# SCH_JTAG_14P_10P_2022-09-26.net
KiCad netlist of a schematic drawn in EasyEDA
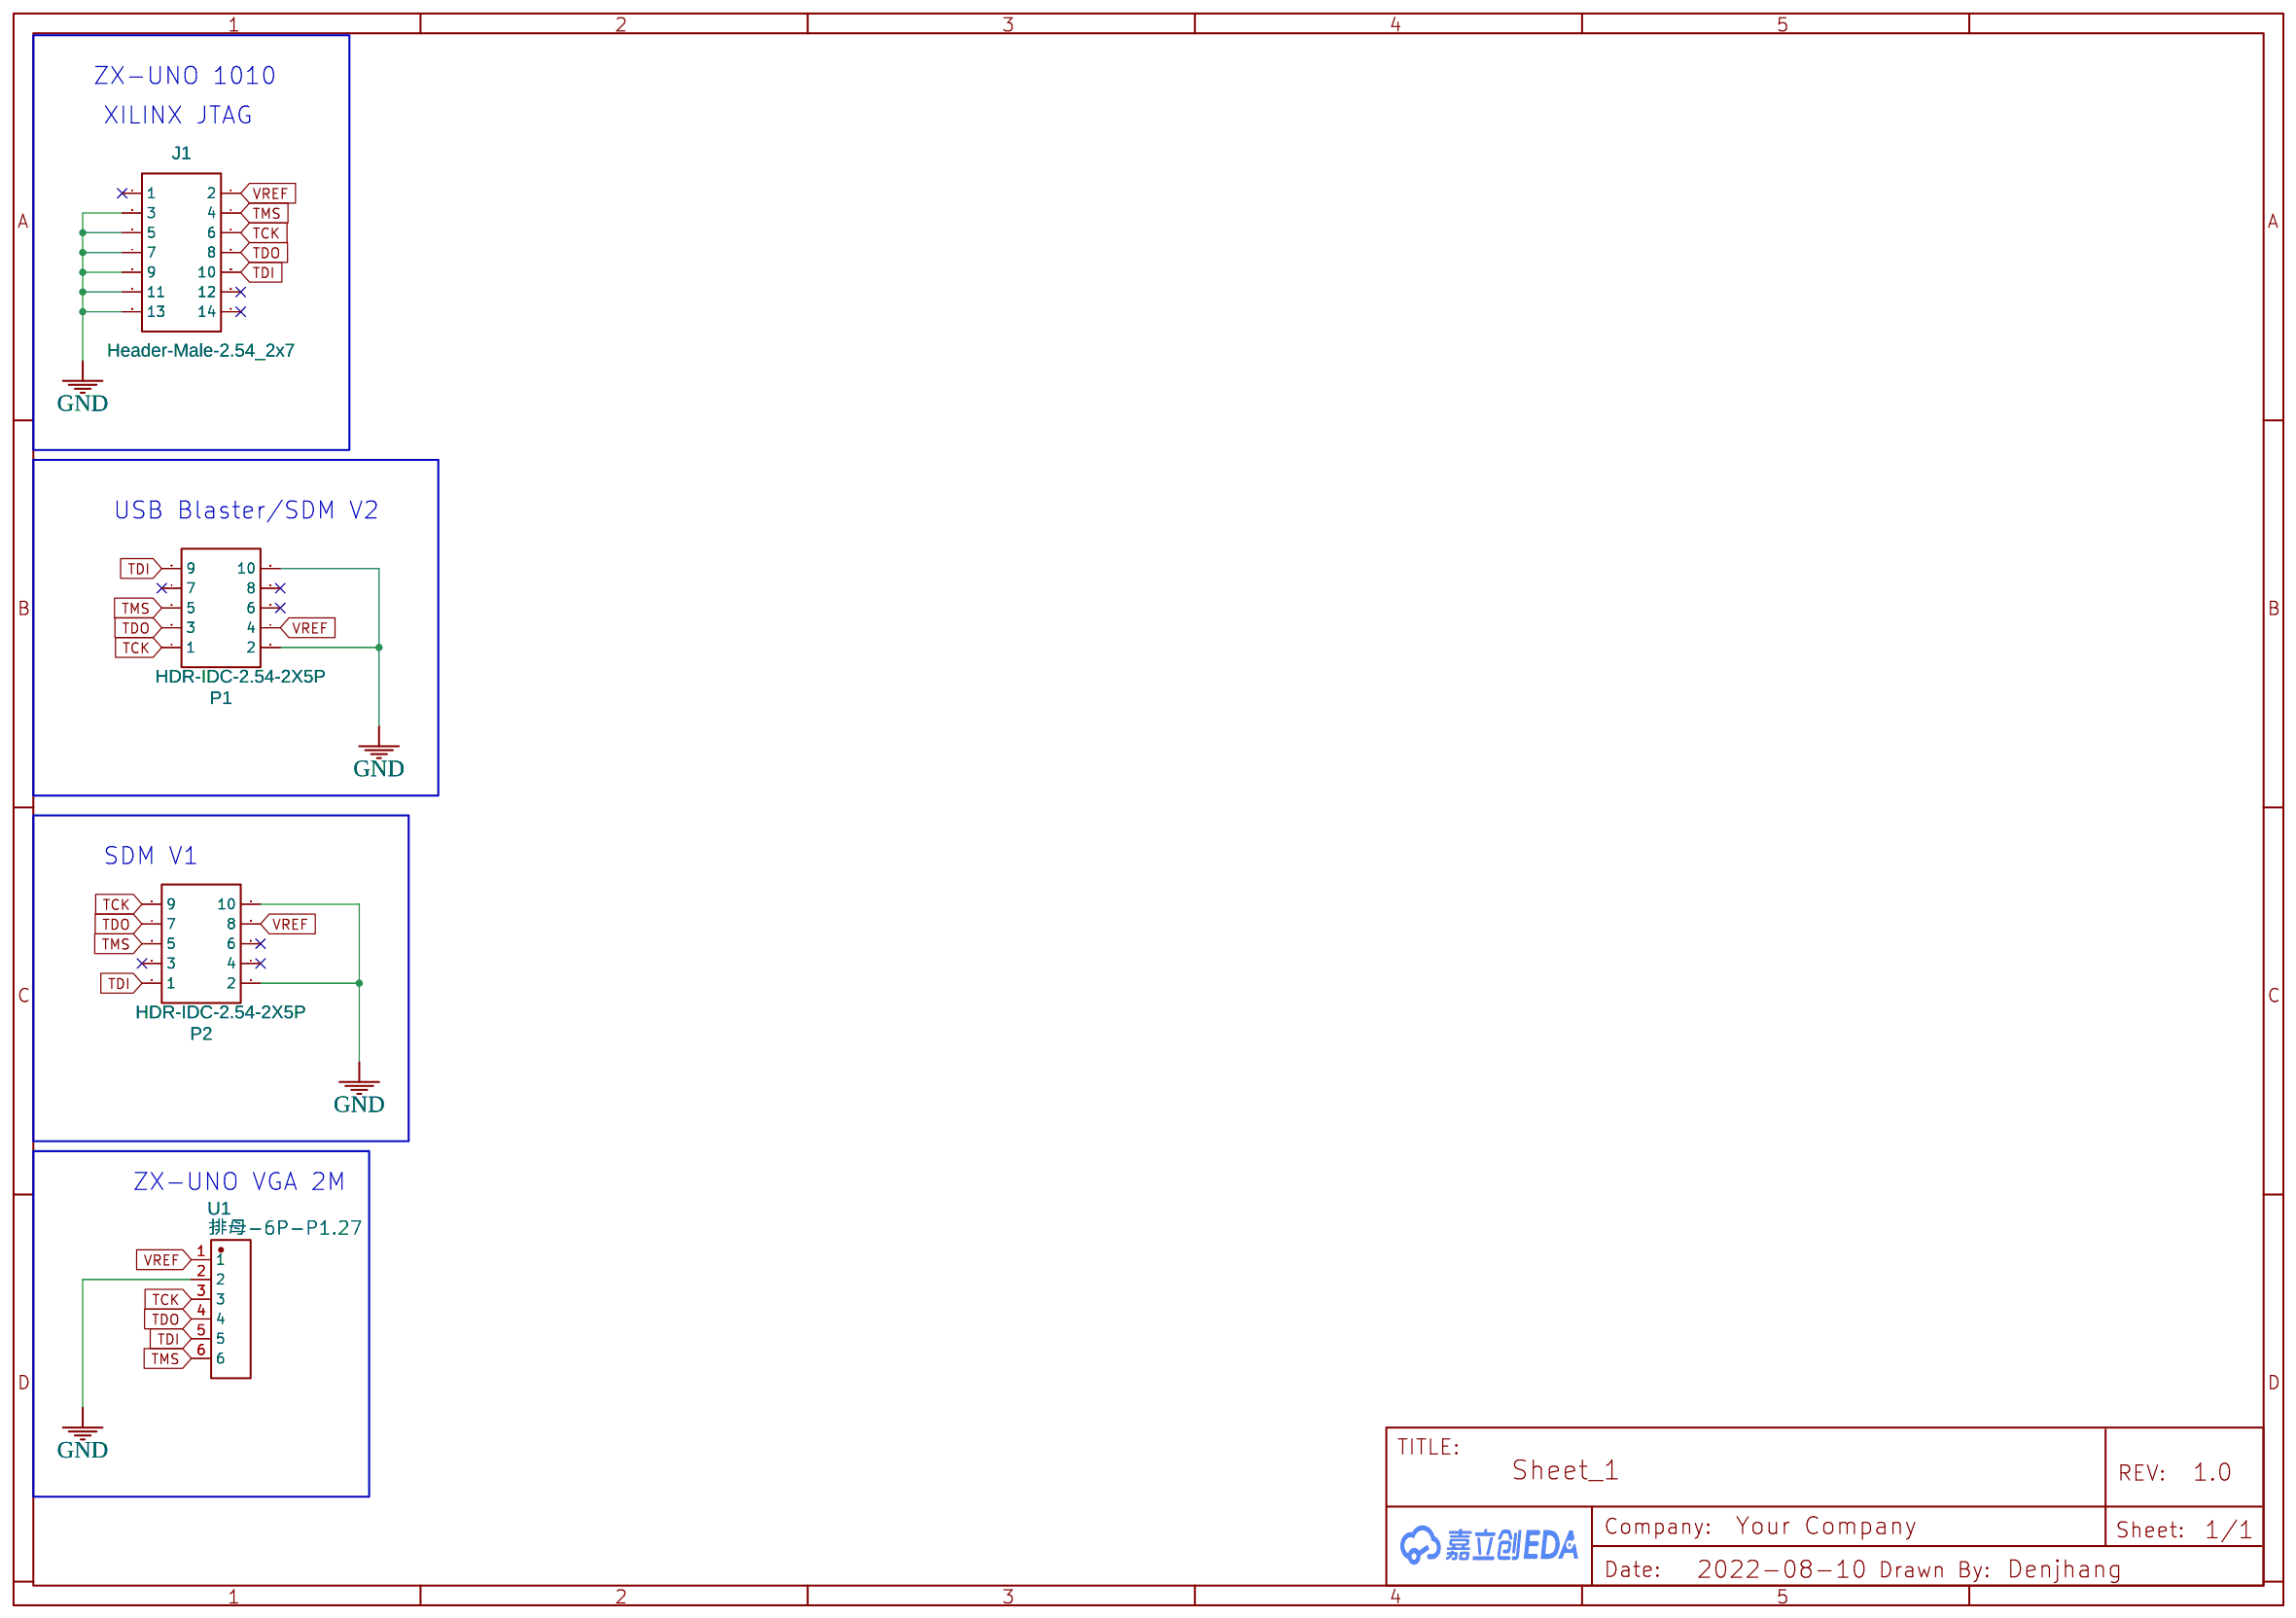
[diagram p0: schematic sheet]

(export (version "E")
  (design (tool "Eeschema 10.0.6"))
  (components
    (comp (ref "J1")
      (value "Header-Male-2.54_2x7")
      (fields
        (field (name "BOM_Manufacturer Part") "Double row of needle2X7P 2.54mm")
        (field (name "BOM_Supplier Part") "C71397")
      )
      (libsource (lib "") (part "Header-Male-2.54_2x7"))
    )
    (comp (ref "P1")
      (value "HDR-IDC-2.54-2X5P")
      (fields
        (field (name "BOM_Manufacturer Part") "IDC Box 2.54mm 2X5P")
        (field (name "BOM_Supplier Part") "C5665")
      )
      (libsource (lib "") (part "HDR-IDC-2.54-2X5P"))
    )
    (comp (ref "P2")
      (value "HDR-IDC-2.54-2X5P")
      (fields
        (field (name "BOM_Manufacturer Part") "IDC Box 2.54mm 2X5P")
        (field (name "BOM_Supplier Part") "C5665")
      )
      (libsource (lib "") (part "HDR-IDC-2.54-2X5P"))
    )
    (comp (ref "U1")
      (value "排母-6P-P1.27")
      (fields
        (field (name "BOM_Manufacturer Part") "KH-1.27FH-1X6P-H4.3")
        (field (name "BOM_Supplier Part") "C2938382")
      )
      (libsource (lib "") (part "排母-6P-P1.27"))
    )
  )
  (nets
    (net (code "1") (name "GND") (class "Default")
      (node (ref "J1") (pin "11") (pinfunction "11_11") (pintype "input"))
      (node (ref "J1") (pin "13") (pinfunction "13_13") (pintype "input"))
      (node (ref "J1") (pin "3") (pinfunction "3_3") (pintype "input"))
      (node (ref "J1") (pin "5") (pinfunction "5_5") (pintype "input"))
      (node (ref "J1") (pin "7") (pinfunction "7_7") (pintype "input"))
      (node (ref "J1") (pin "9") (pinfunction "9_9") (pintype "input"))
      (node (ref "P1") (pin "10") (pinfunction "10_10") (pintype "unspecified"))
      (node (ref "P1") (pin "2") (pinfunction "2_2") (pintype "unspecified"))
      (node (ref "P2") (pin "10") (pinfunction "10_10") (pintype "unspecified"))
      (node (ref "P2") (pin "2") (pinfunction "2_2") (pintype "unspecified"))
      (node (ref "U1") (pin "2") (pinfunction "2_2") (pintype "unspecified"))
    )
    (net (code "2") (name "TCK") (class "Default")
      (node (ref "J1") (pin "6") (pinfunction "6_6") (pintype "input"))
      (node (ref "P1") (pin "1") (pinfunction "1_1") (pintype "unspecified"))
      (node (ref "P2") (pin "9") (pinfunction "9_9") (pintype "unspecified"))
      (node (ref "U1") (pin "3") (pinfunction "3_3") (pintype "unspecified"))
    )
    (net (code "3") (name "TDI") (class "Default")
      (node (ref "J1") (pin "10") (pinfunction "10_10") (pintype "input"))
      (node (ref "P1") (pin "9") (pinfunction "9_9") (pintype "unspecified"))
      (node (ref "P2") (pin "1") (pinfunction "1_1") (pintype "unspecified"))
      (node (ref "U1") (pin "5") (pinfunction "5_5") (pintype "unspecified"))
    )
    (net (code "4") (name "TDO") (class "Default")
      (node (ref "J1") (pin "8") (pinfunction "8_8") (pintype "input"))
      (node (ref "P1") (pin "3") (pinfunction "3_3") (pintype "unspecified"))
      (node (ref "P2") (pin "7") (pinfunction "7_7") (pintype "unspecified"))
      (node (ref "U1") (pin "4") (pinfunction "4_4") (pintype "unspecified"))
    )
    (net (code "5") (name "TMS") (class "Default")
      (node (ref "J1") (pin "4") (pinfunction "4_4") (pintype "input"))
      (node (ref "P1") (pin "5") (pinfunction "5_5") (pintype "unspecified"))
      (node (ref "P2") (pin "5") (pinfunction "5_5") (pintype "unspecified"))
      (node (ref "U1") (pin "6") (pinfunction "6_6") (pintype "unspecified"))
    )
    (net (code "6") (name "VREF") (class "Default")
      (node (ref "J1") (pin "2") (pinfunction "2_2") (pintype "input"))
      (node (ref "P1") (pin "4") (pinfunction "4_4") (pintype "unspecified"))
      (node (ref "P2") (pin "8") (pinfunction "8_8") (pintype "unspecified"))
      (node (ref "U1") (pin "1") (pinfunction "1_1") (pintype "unspecified"))
    )
    (net (code "7") (name "unconnected-(J1-Pad1)") (class "Default")
      (node (ref "J1") (pin "1") (pinfunction "1_1") (pintype "input+no_connect"))
    )
    (net (code "8") (name "unconnected-(J1-Pad12)") (class "Default")
      (node (ref "J1") (pin "12") (pinfunction "12_12") (pintype "input+no_connect"))
    )
    (net (code "9") (name "unconnected-(J1-Pad14)") (class "Default")
      (node (ref "J1") (pin "14") (pinfunction "14_14") (pintype "input+no_connect"))
    )
    (net (code "10") (name "unconnected-(P1-Pad6)") (class "Default")
      (node (ref "P1") (pin "6") (pinfunction "6_6") (pintype "unspecified+no_connect"))
    )
    (net (code "11") (name "unconnected-(P1-Pad7)") (class "Default")
      (node (ref "P1") (pin "7") (pinfunction "7_7") (pintype "unspecified+no_connect"))
    )
    (net (code "12") (name "unconnected-(P1-Pad8)") (class "Default")
      (node (ref "P1") (pin "8") (pinfunction "8_8") (pintype "unspecified+no_connect"))
    )
    (net (code "13") (name "unconnected-(P2-Pad3)") (class "Default")
      (node (ref "P2") (pin "3") (pinfunction "3_3") (pintype "unspecified+no_connect"))
    )
    (net (code "14") (name "unconnected-(P2-Pad4)") (class "Default")
      (node (ref "P2") (pin "4") (pinfunction "4_4") (pintype "unspecified+no_connect"))
    )
    (net (code "15") (name "unconnected-(P2-Pad6)") (class "Default")
      (node (ref "P2") (pin "6") (pinfunction "6_6") (pintype "unspecified+no_connect"))
    )
  )
)
